# working.net
KiCad netlist of a schematic drawn in EAGLE
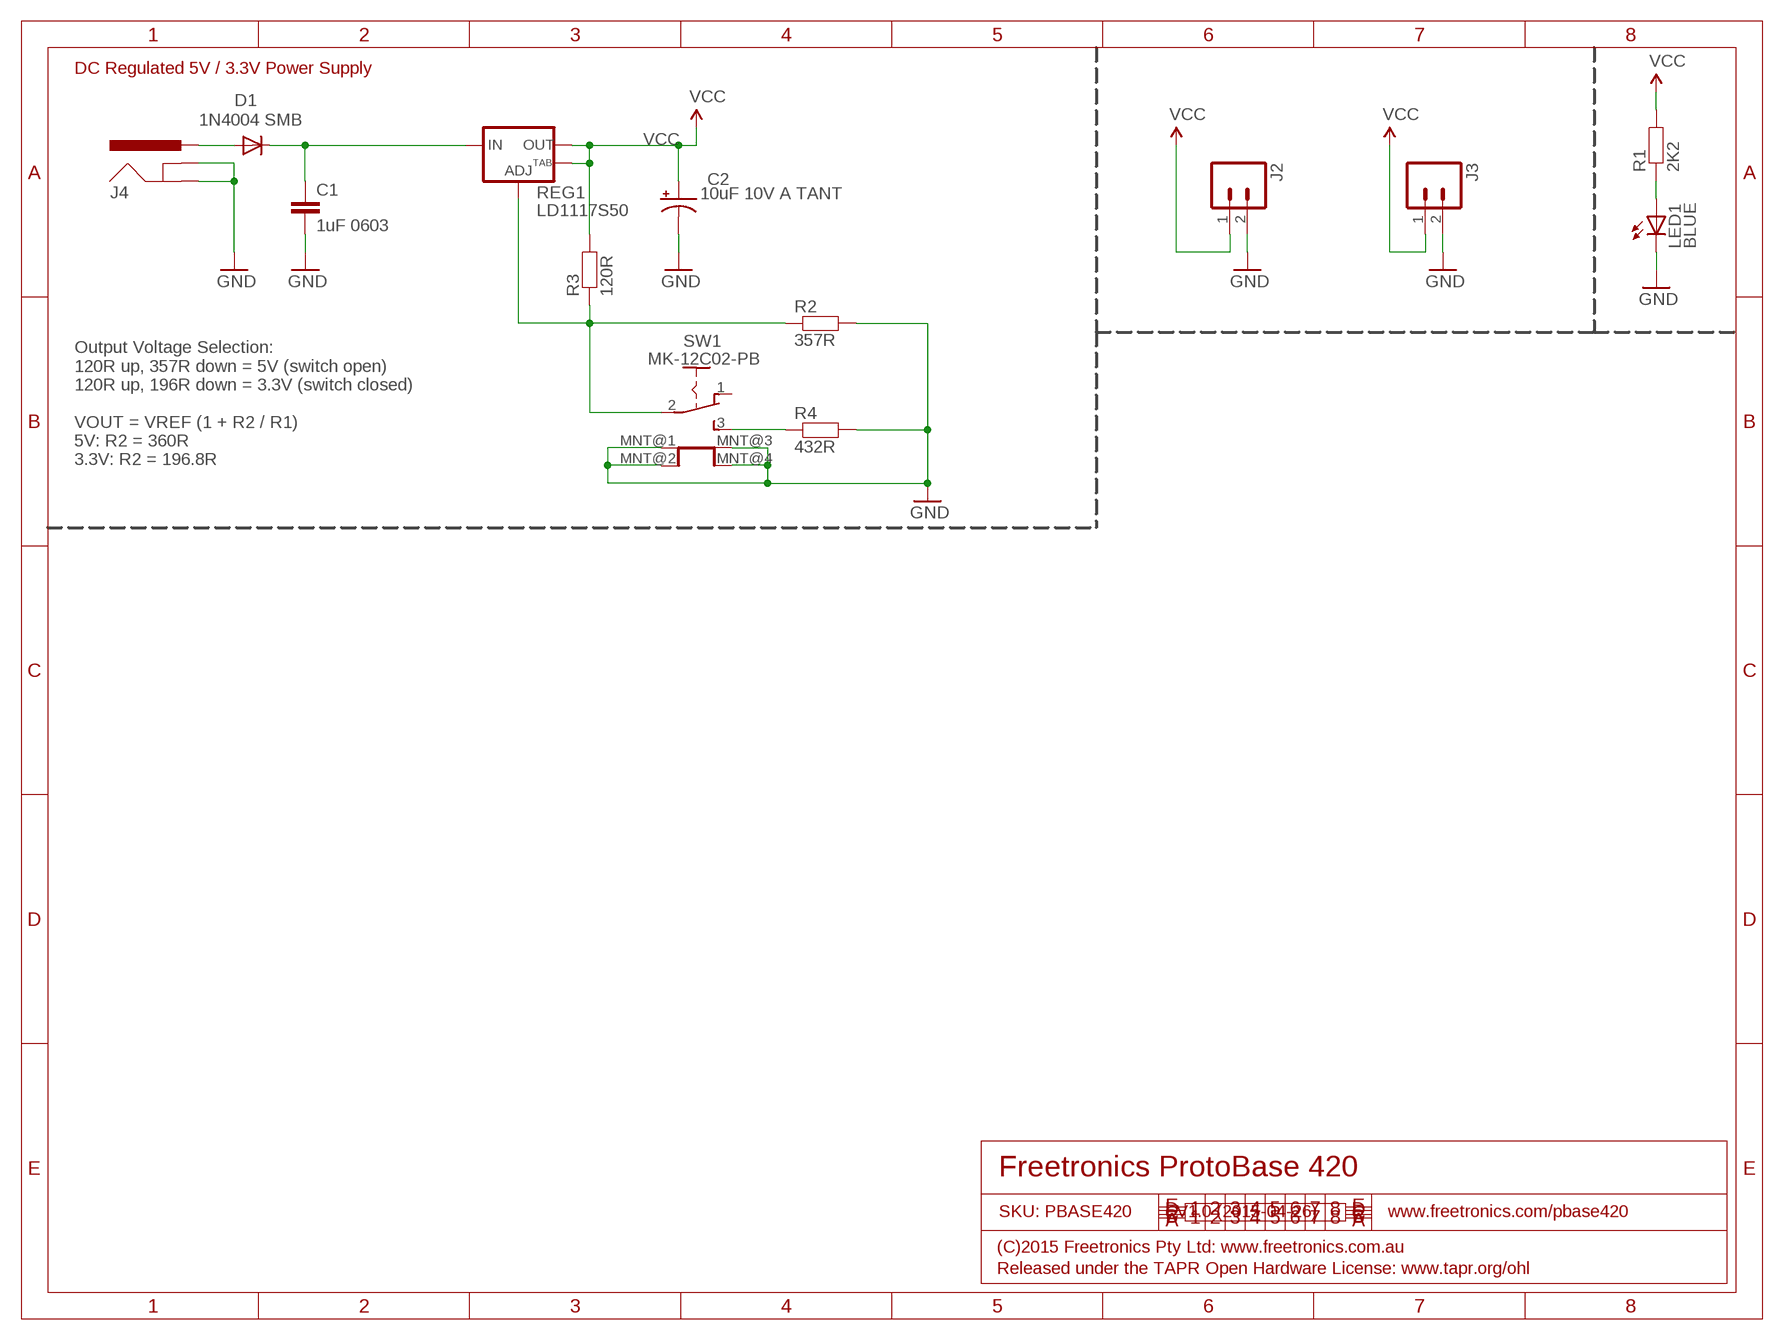
[diagram p0: schematic, sheet 1]

(export (version "E")
  (design (tool "Eeschema 10.0.6"))
  (components
    (comp (ref "C1")
      (value "1uF 0603")
      (footprint "eagle-import:0603")
      (libsource (lib "eagle-import") (part "CAP0603"))
    )
    (comp (ref "C2")
      (value "10uF 10V A TANT")
      (footprint "eagle-import:EIA3216")
      (libsource (lib "eagle-import") (part "CAP_POL1206"))
    )
    (comp (ref "D1")
      (value "1N4004 SMB")
      (footprint "eagle-import:SMB-DIODE")
      (libsource (lib "eagle-import") (part "DIODESMB"))
    )
    (comp (ref "J2")
      (value "M02PTH")
      (footprint "eagle-import:1X02")
      (libsource (lib "eagle-import") (part "M02PTH"))
    )
    (comp (ref "J3")
      (value "M02PTH")
      (footprint "eagle-import:1X02")
      (libsource (lib "eagle-import") (part "M02PTH"))
    )
    (comp (ref "J4")
      (value "POWER_JACKPTH_SLOTS")
      (footprint "eagle-import:POWER_JACK_PTH_SLOTS")
      (libsource (lib "eagle-import") (part "POWER_JACKPTH_SLOTS"))
    )
    (comp (ref "LED1")
      (value "BLUE")
      (footprint "eagle-import:LED-0603")
      (libsource (lib "eagle-import") (part "LED0603"))
    )
    (comp (ref "R1")
      (value "2K2")
      (footprint "eagle-import:0603")
      (libsource (lib "eagle-import") (part "RESISTOR0603"))
    )
    (comp (ref "R2")
      (value "357R")
      (footprint "eagle-import:0603")
      (libsource (lib "eagle-import") (part "RESISTOR0603"))
    )
    (comp (ref "R3")
      (value "120R")
      (footprint "eagle-import:0603")
      (libsource (lib "eagle-import") (part "RESISTOR0603"))
    )
    (comp (ref "R4")
      (value "432R")
      (footprint "eagle-import:0603")
      (libsource (lib "eagle-import") (part "RESISTOR0603"))
    )
    (comp (ref "REG1")
      (value "LD1117S50")
      (footprint "eagle-import:SOT223")
      (libsource (lib "eagle-import") (part "V_REG_LM1117SOT223"))
    )
    (comp (ref "SW1")
      (value "MK-12C02-PB")
      (footprint "eagle-import:MK-12C02")
      (libsource (lib "eagle-import") (part "SWITCH-SPDT-4TABSSMT"))
    )
  )
  (nets
    (net (code "1") (name "GND") (class "Default")
      (node (ref "C1") (pin "2") (pinfunction "2_2") (pintype "passive"))
      (node (ref "C2") (pin "C") (pinfunction "-_C") (pintype "passive"))
      (node (ref "J2") (pin "2") (pinfunction "2_2") (pintype "passive"))
      (node (ref "J3") (pin "2") (pinfunction "2_2") (pintype "passive"))
      (node (ref "J4") (pin "GND") (pinfunction "GND_GND") (pintype "bidirectional"))
      (node (ref "J4") (pin "GNDBREAK") (pinfunction "GNDBREAK_GNDBREAK") (pintype "bidirectional"))
      (node (ref "LED1") (pin "C") (pinfunction "C_C") (pintype "passive"))
      (node (ref "R2") (pin "2") (pinfunction "2_2") (pintype "passive"))
      (node (ref "R4") (pin "2") (pinfunction "2_2") (pintype "passive"))
      (node (ref "SW1") (pin "MNT@1") (pinfunction "MNT_MNT@1") (pintype "bidirectional"))
      (node (ref "SW1") (pin "MNT@2") (pinfunction "MNT_MNT@2") (pintype "bidirectional"))
      (node (ref "SW1") (pin "MNT@3") (pinfunction "MNT_MNT@3") (pintype "bidirectional"))
      (node (ref "SW1") (pin "MNT@4") (pinfunction "MNT_MNT@4") (pintype "bidirectional"))
    )
    (net (code "2") (name "Net-(D1-PadA)") (class "Default")
      (node (ref "D1") (pin "A") (pinfunction "A_A") (pintype "passive"))
      (node (ref "J4") (pin "PWR") (pinfunction "PWR_PWR") (pintype "bidirectional"))
    )
    (net (code "3") (name "Net-(LED1-PadA)") (class "Default")
      (node (ref "LED1") (pin "A") (pinfunction "A_A") (pintype "passive"))
      (node (ref "R1") (pin "1") (pinfunction "1_1") (pintype "passive"))
    )
    (net (code "4") (name "Net-(REG1-ADJ)") (class "Default")
      (node (ref "R2") (pin "1") (pinfunction "1_1") (pintype "passive"))
      (node (ref "R3") (pin "1") (pinfunction "1_1") (pintype "passive"))
      (node (ref "REG1") (pin "1") (pinfunction "ADJ_1") (pintype "input"))
      (node (ref "SW1") (pin "2") (pinfunction "COM_2") (pintype "passive"))
    )
    (net (code "5") (name "Net-(REG1-IN)") (class "Default")
      (node (ref "C1") (pin "1") (pinfunction "1_1") (pintype "passive"))
      (node (ref "D1") (pin "C") (pinfunction "C_C") (pintype "passive"))
      (node (ref "REG1") (pin "3") (pinfunction "IN_3") (pintype "input"))
    )
    (net (code "6") (name "Net-(SW1-B)") (class "Default")
      (node (ref "R4") (pin "1") (pinfunction "1_1") (pintype "passive"))
      (node (ref "SW1") (pin "3") (pinfunction "B_3") (pintype "passive"))
    )
    (net (code "7") (name "VCC") (class "Default")
      (node (ref "C2") (pin "A") (pinfunction "+_A") (pintype "passive"))
      (node (ref "J2") (pin "1") (pinfunction "1_1") (pintype "passive"))
      (node (ref "J3") (pin "1") (pinfunction "1_1") (pintype "passive"))
      (node (ref "R1") (pin "2") (pinfunction "2_2") (pintype "passive"))
      (node (ref "R3") (pin "2") (pinfunction "2_2") (pintype "passive"))
      (node (ref "REG1") (pin "2") (pinfunction "OUT_2") (pintype "output"))
      (node (ref "REG1") (pin "4") (pinfunction "OUT_4") (pintype "output"))
    )
    (net (code "8") (name "unconnected-(SW1-A-Pad1)") (class "Default")
      (node (ref "SW1") (pin "1") (pinfunction "A_1") (pintype "passive"))
    )
  )
)
